# MODUL_ADC_V101.net
KiCad netlist of a schematic drawn in EAGLE
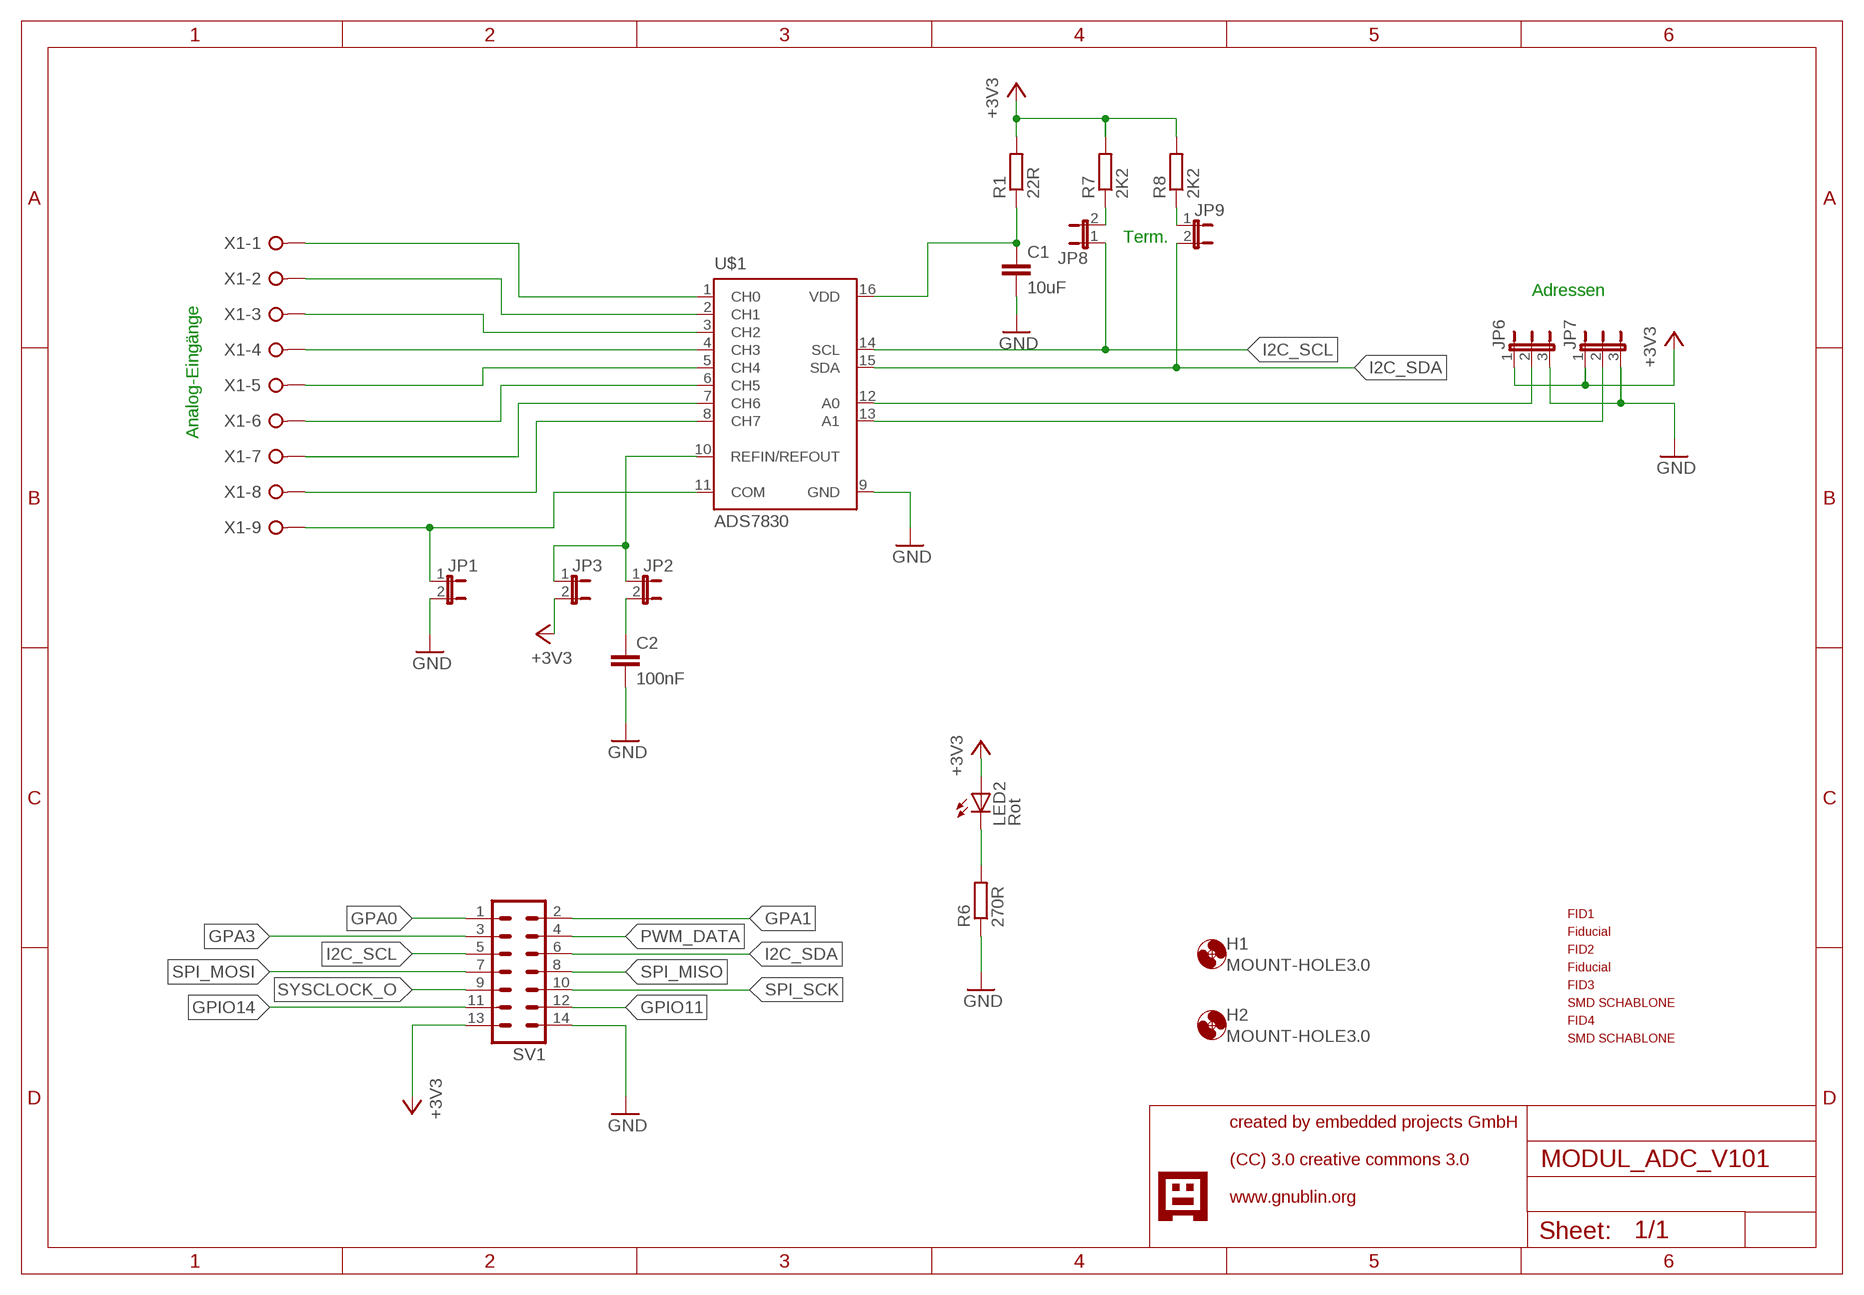
[diagram p0: schematic, sheet 1]

(export (version "E")
  (design (tool "Eeschema 10.0.6"))
  (components
    (comp (ref "C1")
      (value "10uF")
      (footprint "eagle-import:C0805")
      (libsource (lib "eagle-import") (part "C-EUC0805"))
    )
    (comp (ref "C2")
      (value "100nF")
      (footprint "eagle-import:C0805")
      (libsource (lib "eagle-import") (part "C-EUC0805"))
    )
    (comp (ref "FID1")
      (value "PASSERMARKEN_FIDUCIAL")
      (footprint "eagle-import:PASSERMARKEN_FIDUCIAL")
      (libsource (lib "eagle-import") (part "PASSERMARKEN_FIDUCIAL"))
    )
    (comp (ref "FID2")
      (value "PASSERMARKEN_FIDUCIAL")
      (footprint "eagle-import:PASSERMARKEN_FIDUCIAL")
      (libsource (lib "eagle-import") (part "PASSERMARKEN_FIDUCIAL"))
    )
    (comp (ref "FID3")
      (value "PASSERMARKEN_FIDUCIAL")
      (footprint "eagle-import:PASSERMARKEN_FIDUCIAL")
      (libsource (lib "eagle-import") (part "SMDSCHABLONE_PASSERMARKEN_FIDUCIAL"))
    )
    (comp (ref "FID4")
      (value "PASSERMARKEN_FIDUCIAL")
      (footprint "eagle-import:PASSERMARKEN_FIDUCIAL")
      (libsource (lib "eagle-import") (part "SMDSCHABLONE_PASSERMARKEN_FIDUCIAL"))
    )
    (comp (ref "H1")
      (value "MOUNT-HOLE3.0")
      (footprint "eagle-import:3,0")
      (libsource (lib "eagle-import") (part "MOUNT-HOLE3.0"))
    )
    (comp (ref "H2")
      (value "MOUNT-HOLE3.0")
      (footprint "eagle-import:3,0")
      (libsource (lib "eagle-import") (part "MOUNT-HOLE3.0"))
    )
    (comp (ref "JP1")
      (value "JP1E")
      (footprint "eagle-import:JP1")
      (libsource (lib "eagle-import") (part "JP1E"))
    )
    (comp (ref "JP2")
      (value "JP1E")
      (footprint "eagle-import:JP1")
      (libsource (lib "eagle-import") (part "JP1E"))
    )
    (comp (ref "JP3")
      (value "JP1E")
      (footprint "eagle-import:JP1")
      (libsource (lib "eagle-import") (part "JP1E"))
    )
    (comp (ref "JP6")
      (value "JP2E")
      (footprint "eagle-import:JP2")
      (libsource (lib "eagle-import") (part "JP2E"))
    )
    (comp (ref "JP7")
      (value "JP2E")
      (footprint "eagle-import:JP2")
      (libsource (lib "eagle-import") (part "JP2E"))
    )
    (comp (ref "JP8")
      (value "JP1E")
      (footprint "eagle-import:JP1")
      (libsource (lib "eagle-import") (part "JP1E"))
    )
    (comp (ref "JP9")
      (value "JP1E")
      (footprint "eagle-import:JP1")
      (libsource (lib "eagle-import") (part "JP1E"))
    )
    (comp (ref "LED2")
      (value "Rot")
      (footprint "eagle-import:CHIP-LED0805")
      (libsource (lib "eagle-import") (part "LEDCHIP-LED0805"))
    )
    (comp (ref "R1")
      (value "22R")
      (footprint "eagle-import:R0805")
      (libsource (lib "eagle-import") (part "R-EU_R0805"))
    )
    (comp (ref "R6")
      (value "270R")
      (footprint "eagle-import:R0805")
      (libsource (lib "eagle-import") (part "R-EU_R0805"))
    )
    (comp (ref "R7")
      (value "2K2")
      (footprint "eagle-import:R0805")
      (libsource (lib "eagle-import") (part "R-EU_R0805"))
    )
    (comp (ref "R8")
      (value "2K2")
      (footprint "eagle-import:R0805")
      (libsource (lib "eagle-import") (part "R-EU_R0805"))
    )
    (comp (ref "SV1")
      (value "ML14")
      (footprint "eagle-import:ML14")
      (libsource (lib "eagle-import") (part "ML14"))
    )
    (comp (ref "U$1")
      (value "ADS7830")
      (footprint "eagle-import:TSSOP16")
      (libsource (lib "eagle-import") (part "ADS7830"))
    )
    (comp (ref "U$2")
      (value "GNUBLINLOGOSIEB")
      (footprint "eagle-import:GNUSIEBDRUCK")
      (libsource (lib "eagle-import") (part "GNUBLINLOGOSIEB"))
    )
    (comp (ref "X1")
      (value "W237-09P")
      (footprint "eagle-import:W237-9P")
      (libsource (lib "eagle-import") (part "W237-09P"))
    )
  )
  (nets
    (net (code "1") (name "+3V3") (class "Default")
      (node (ref "JP3") (pin "2") (pinfunction "2_2") (pintype "passive"))
      (node (ref "JP6") (pin "1") (pinfunction "1_1") (pintype "passive"))
      (node (ref "JP7") (pin "1") (pinfunction "1_1") (pintype "passive"))
      (node (ref "LED2") (pin "A") (pinfunction "A_A") (pintype "passive"))
      (node (ref "R1") (pin "2") (pinfunction "2_2") (pintype "passive"))
      (node (ref "R7") (pin "2") (pinfunction "2_2") (pintype "passive"))
      (node (ref "R8") (pin "2") (pinfunction "2_2") (pintype "passive"))
      (node (ref "SV1") (pin "13") (pinfunction "13_13") (pintype "passive"))
    )
    (net (code "2") (name "GND") (class "Default")
      (node (ref "C1") (pin "2") (pinfunction "2_2") (pintype "passive"))
      (node (ref "C2") (pin "2") (pinfunction "2_2") (pintype "passive"))
      (node (ref "JP1") (pin "2") (pinfunction "2_2") (pintype "passive"))
      (node (ref "JP6") (pin "3") (pinfunction "3_3") (pintype "passive"))
      (node (ref "JP7") (pin "3") (pinfunction "3_3") (pintype "passive"))
      (node (ref "R6") (pin "1") (pinfunction "1_1") (pintype "passive"))
      (node (ref "SV1") (pin "14") (pinfunction "14_14") (pintype "passive"))
      (node (ref "U$1") (pin "9") (pinfunction "GND_9") (pintype "power_in"))
    )
    (net (code "3") (name "GPA0") (class "Default")
      (node (ref "SV1") (pin "1") (pinfunction "1_1") (pintype "passive"))
    )
    (net (code "4") (name "GPA1") (class "Default")
      (node (ref "SV1") (pin "2") (pinfunction "2_2") (pintype "passive"))
    )
    (net (code "5") (name "GPA3") (class "Default")
      (node (ref "SV1") (pin "3") (pinfunction "3_3") (pintype "passive"))
    )
    (net (code "6") (name "GPIO11") (class "Default")
      (node (ref "SV1") (pin "12") (pinfunction "12_12") (pintype "passive"))
    )
    (net (code "7") (name "GPIO14") (class "Default")
      (node (ref "SV1") (pin "11") (pinfunction "11_11") (pintype "passive"))
    )
    (net (code "8") (name "I2C_SCL") (class "Default")
      (node (ref "JP8") (pin "1") (pinfunction "1_1") (pintype "passive"))
      (node (ref "SV1") (pin "5") (pinfunction "5_5") (pintype "passive"))
      (node (ref "U$1") (pin "14") (pinfunction "SCL_14") (pintype "input"))
    )
    (net (code "9") (name "I2C_SDA") (class "Default")
      (node (ref "JP9") (pin "2") (pinfunction "2_2") (pintype "passive"))
      (node (ref "SV1") (pin "6") (pinfunction "6_6") (pintype "passive"))
      (node (ref "U$1") (pin "15") (pinfunction "SDA_15") (pintype "bidirectional"))
    )
    (net (code "10") (name "Net-(C2-Pad1)") (class "Default")
      (node (ref "C2") (pin "1") (pinfunction "1_1") (pintype "passive"))
      (node (ref "JP2") (pin "2") (pinfunction "2_2") (pintype "passive"))
    )
    (net (code "11") (name "Net-(JP8-Pad2)") (class "Default")
      (node (ref "JP8") (pin "2") (pinfunction "2_2") (pintype "passive"))
      (node (ref "R7") (pin "1") (pinfunction "1_1") (pintype "passive"))
    )
    (net (code "12") (name "Net-(JP9-Pad1)") (class "Default")
      (node (ref "JP9") (pin "1") (pinfunction "1_1") (pintype "passive"))
      (node (ref "R8") (pin "1") (pinfunction "1_1") (pintype "passive"))
    )
    (net (code "13") (name "Net-(LED2-PadC)") (class "Default")
      (node (ref "LED2") (pin "C") (pinfunction "C_C") (pintype "passive"))
      (node (ref "R6") (pin "2") (pinfunction "2_2") (pintype "passive"))
    )
    (net (code "14") (name "Net-(U$1-A0)") (class "Default")
      (node (ref "JP6") (pin "2") (pinfunction "2_2") (pintype "passive"))
      (node (ref "U$1") (pin "12") (pinfunction "A0_12") (pintype "input"))
    )
    (net (code "15") (name "Net-(U$1-A1)") (class "Default")
      (node (ref "JP7") (pin "2") (pinfunction "2_2") (pintype "passive"))
      (node (ref "U$1") (pin "13") (pinfunction "A1_13") (pintype "input"))
    )
    (net (code "16") (name "Net-(U$1-CH0)") (class "Default")
      (node (ref "U$1") (pin "1") (pinfunction "CH0_1") (pintype "input"))
      (node (ref "X1") (pin "1") (pinfunction "KL_1") (pintype "passive"))
    )
    (net (code "17") (name "Net-(U$1-CH1)") (class "Default")
      (node (ref "U$1") (pin "2") (pinfunction "CH1_2") (pintype "input"))
      (node (ref "X1") (pin "2") (pinfunction "KL_2") (pintype "passive"))
    )
    (net (code "18") (name "Net-(U$1-CH2)") (class "Default")
      (node (ref "U$1") (pin "3") (pinfunction "CH2_3") (pintype "input"))
      (node (ref "X1") (pin "3") (pinfunction "KL_3") (pintype "passive"))
    )
    (net (code "19") (name "Net-(U$1-CH3)") (class "Default")
      (node (ref "U$1") (pin "4") (pinfunction "CH3_4") (pintype "input"))
      (node (ref "X1") (pin "4") (pinfunction "KL_4") (pintype "passive"))
    )
    (net (code "20") (name "Net-(U$1-CH4)") (class "Default")
      (node (ref "U$1") (pin "5") (pinfunction "CH4_5") (pintype "input"))
      (node (ref "X1") (pin "5") (pinfunction "KL_5") (pintype "passive"))
    )
    (net (code "21") (name "Net-(U$1-CH5)") (class "Default")
      (node (ref "U$1") (pin "6") (pinfunction "CH5_6") (pintype "input"))
      (node (ref "X1") (pin "6") (pinfunction "KL_6") (pintype "passive"))
    )
    (net (code "22") (name "Net-(U$1-CH6)") (class "Default")
      (node (ref "U$1") (pin "7") (pinfunction "CH6_7") (pintype "input"))
      (node (ref "X1") (pin "7") (pinfunction "KL_7") (pintype "passive"))
    )
    (net (code "23") (name "Net-(U$1-CH7)") (class "Default")
      (node (ref "U$1") (pin "8") (pinfunction "CH7_8") (pintype "input"))
      (node (ref "X1") (pin "8") (pinfunction "KL_8") (pintype "passive"))
    )
    (net (code "24") (name "Net-(U$1-COM)") (class "Default")
      (node (ref "JP1") (pin "1") (pinfunction "1_1") (pintype "passive"))
      (node (ref "U$1") (pin "11") (pinfunction "COM_11") (pintype "input"))
      (node (ref "X1") (pin "9") (pinfunction "KL_9") (pintype "passive"))
    )
    (net (code "25") (name "Net-(U$1-REFIN{slash}REFOUT)") (class "Default")
      (node (ref "JP2") (pin "1") (pinfunction "1_1") (pintype "passive"))
      (node (ref "JP3") (pin "1") (pinfunction "1_1") (pintype "passive"))
      (node (ref "U$1") (pin "10") (pinfunction "REFIN/REFOUT_10") (pintype "passive"))
    )
    (net (code "26") (name "Net-(U$1-VDD)") (class "Default")
      (node (ref "C1") (pin "1") (pinfunction "1_1") (pintype "passive"))
      (node (ref "R1") (pin "1") (pinfunction "1_1") (pintype "passive"))
      (node (ref "U$1") (pin "16") (pinfunction "VDD_16") (pintype "power_in"))
    )
    (net (code "27") (name "PWM_DATA") (class "Default")
      (node (ref "SV1") (pin "4") (pinfunction "4_4") (pintype "passive"))
    )
    (net (code "28") (name "SPI_MISO") (class "Default")
      (node (ref "SV1") (pin "8") (pinfunction "8_8") (pintype "passive"))
    )
    (net (code "29") (name "SPI_MOSI") (class "Default")
      (node (ref "SV1") (pin "7") (pinfunction "7_7") (pintype "passive"))
    )
    (net (code "30") (name "SPI_SCK") (class "Default")
      (node (ref "SV1") (pin "10") (pinfunction "10_10") (pintype "passive"))
    )
    (net (code "31") (name "SYSCLOCK_O") (class "Default")
      (node (ref "SV1") (pin "9") (pinfunction "9_9") (pintype "passive"))
    )
  )
)
